# LDO.net
KiCad netlist of a schematic drawn in Altium Designer
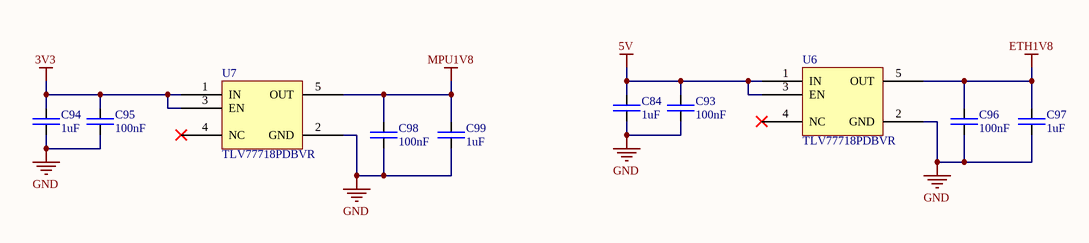
[diagram p0: LDO.SchDoc]

(export (version "E")
  (design (tool "Eeschema 10.0.6"))
  (components
    (comp (ref "C84")
      (value "1uF")
      (footprint "CAP-0805")
      (description "Capacitor chip unpolarized. 0805")
      (libsource (lib "Master") (part "CAP-0805"))
    )
    (comp (ref "C93")
      (value "100nF")
      (footprint "CAP-0603")
      (description "Capacitor chip unpolarized. 0603")
      (libsource (lib "Master") (part "CAP-0603"))
    )
    (comp (ref "C94")
      (value "1uF")
      (footprint "CAP-0805")
      (description "Capacitor chip unpolarized. 0805")
      (libsource (lib "Master") (part "CAP-0805"))
    )
    (comp (ref "C95")
      (value "100nF")
      (footprint "CAP-0603")
      (description "Capacitor chip unpolarized. 0603")
      (libsource (lib "Master") (part "CAP-0603"))
    )
    (comp (ref "C96")
      (value "100nF")
      (footprint "CAP-0603")
      (description "Capacitor chip unpolarized. 0603")
      (libsource (lib "Master") (part "CAP-0603"))
    )
    (comp (ref "C97")
      (value "1uF")
      (footprint "CAP-0805")
      (description "Capacitor chip unpolarized. 0805")
      (libsource (lib "Master") (part "CAP-0805"))
    )
    (comp (ref "C98")
      (value "100nF")
      (footprint "CAP-0603")
      (description "Capacitor chip unpolarized. 0603")
      (libsource (lib "Master") (part "CAP-0603"))
    )
    (comp (ref "C99")
      (value "1uF")
      (footprint "CAP-0805")
      (description "Capacitor chip unpolarized. 0805")
      (libsource (lib "Master") (part "CAP-0805"))
    )
    (comp (ref "U6")
      (value "TLV77718PDBVR")
      (footprint "TLV77718PDBVR")
      (description "LDO 1.8V 1A")
      (libsource (lib "Master") (part "TLV77718PDBVR"))
    )
    (comp (ref "U7")
      (value "TLV77718PDBVR")
      (footprint "TLV77718PDBVR")
      (description "LDO 1.8V 1A")
      (libsource (lib "Master") (part "TLV77718PDBVR"))
    )
  )
  (nets
    (net (code "1") (name "3V3") (class "Default")
      (node (ref "C94") (pin "2") (pintype "passive"))
      (node (ref "C95") (pin "2") (pintype "passive"))
      (node (ref "U7") (pin "1") (pinfunction "IN_1") (pintype "passive"))
      (node (ref "U7") (pin "3") (pinfunction "EN_3") (pintype "passive"))
    )
    (net (code "2") (name "5V") (class "Default")
      (node (ref "C84") (pin "2") (pintype "passive"))
      (node (ref "C93") (pin "2") (pintype "passive"))
      (node (ref "U6") (pin "1") (pinfunction "IN_1") (pintype "passive"))
      (node (ref "U6") (pin "3") (pinfunction "EN_3") (pintype "passive"))
    )
    (net (code "3") (name "ETH1V8") (class "Default")
      (node (ref "C96") (pin "2") (pintype "passive"))
      (node (ref "C97") (pin "2") (pintype "passive"))
      (node (ref "U6") (pin "5") (pinfunction "OUT_5") (pintype "passive"))
    )
    (net (code "4") (name "GND") (class "Default")
      (node (ref "C84") (pin "1") (pintype "passive"))
      (node (ref "C93") (pin "1") (pintype "passive"))
      (node (ref "C94") (pin "1") (pintype "passive"))
      (node (ref "C95") (pin "1") (pintype "passive"))
      (node (ref "C96") (pin "1") (pintype "passive"))
      (node (ref "C97") (pin "1") (pintype "passive"))
      (node (ref "C98") (pin "1") (pintype "passive"))
      (node (ref "C99") (pin "1") (pintype "passive"))
      (node (ref "U6") (pin "2") (pinfunction "GND_2") (pintype "passive"))
      (node (ref "U7") (pin "2") (pinfunction "GND_2") (pintype "passive"))
    )
    (net (code "5") (name "MPU1V8") (class "Default")
      (node (ref "C98") (pin "2") (pintype "passive"))
      (node (ref "C99") (pin "2") (pintype "passive"))
      (node (ref "U7") (pin "5") (pinfunction "OUT_5") (pintype "passive"))
    )
    (net (code "6") (name "unconnected-(U6-NC-Pad4)") (class "Default")
      (node (ref "U6") (pin "4") (pinfunction "NC_4") (pintype "passive+no_connect"))
    )
    (net (code "7") (name "unconnected-(U7-NC-Pad4)") (class "Default")
      (node (ref "U7") (pin "4") (pinfunction "NC_4") (pintype "passive+no_connect"))
    )
  )
)
